# test_anta.net
KiCad netlist of a schematic drawn in Altium Designer
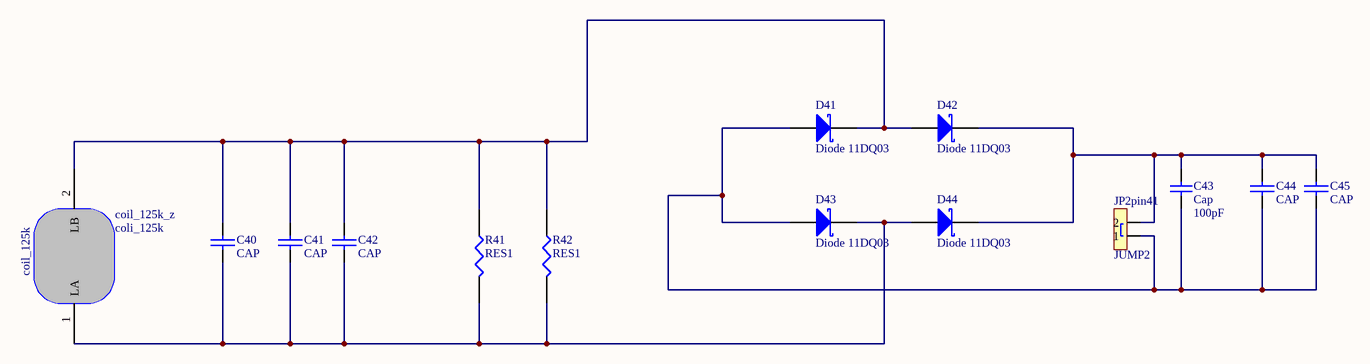
[diagram p0: test_anta.SchDoc]

(export (version "E")
  (design (tool "Eeschema 10.0.6"))
  (components
    (comp (ref "C40")
      (value "CAP")
      (footprint "C0805")
      (description "一般瓷片电容、直插选用RAD0.1，贴片选用0805")
      (libsource (lib "zqq_fmsh") (part "CAP"))
    )
    (comp (ref "C41")
      (value "CAP")
      (footprint "C0805")
      (description "一般瓷片电容、直插选用RAD0.1，贴片选用0805")
      (libsource (lib "zqq_fmsh") (part "CAP"))
    )
    (comp (ref "C42")
      (value "CAP")
      (footprint "RAD-0.3")
      (description "一般瓷片电容、直插选用RAD0.1，贴片选用0805")
      (libsource (lib "zqq_fmsh") (part "CAP"))
    )
    (comp (ref "C43")
      (value "Cap")
      (footprint "RAD-0.3")
      (description "Capacitor")
      (fields (field (name "ALTIUM_VALUE") "100pF") (field (name "PUBLISHER") "Altium Limited"))
      (libsource (lib "Miscellaneous Devices") (part "Cap"))
    )
    (comp (ref "C44")
      (value "CAP")
      (footprint "C0805")
      (description "一般瓷片电容、直插选用RAD0.1，贴片选用0805")
      (libsource (lib "zqq_fmsh") (part "CAP"))
    )
    (comp (ref "C45")
      (value "CAP")
      (footprint "C0805")
      (description "一般瓷片电容、直插选用RAD0.1，贴片选用0805")
      (libsource (lib "zqq_fmsh") (part "CAP"))
    )
    (comp (ref "coil_125k_z")
      (value "coli_125k")
      (footprint "coil_125k")
      (libsource (lib "pke") (part "coli_125k"))
    )
    (comp (ref "D41")
      (value "Diode 11DQ03")
      (footprint "DO-204AL")
      (description "Schottky Rectifier")
      (fields (field (name "PUBLISHER") "Altium Limited"))
      (libsource (lib "Miscellaneous Devices") (part "Diode 11DQ03"))
    )
    (comp (ref "D42")
      (value "Diode 11DQ03")
      (footprint "DO-204AL")
      (description "Schottky Rectifier")
      (fields (field (name "PUBLISHER") "Altium Limited"))
      (libsource (lib "Miscellaneous Devices") (part "Diode 11DQ03"))
    )
    (comp (ref "D43")
      (value "Diode 11DQ03")
      (footprint "DO-204AL")
      (description "Schottky Rectifier")
      (fields (field (name "PUBLISHER") "Altium Limited"))
      (libsource (lib "Miscellaneous Devices") (part "Diode 11DQ03"))
    )
    (comp (ref "D44")
      (value "Diode 11DQ03")
      (footprint "DO-204AL")
      (description "Schottky Rectifier")
      (fields (field (name "PUBLISHER") "Altium Limited"))
      (libsource (lib "Miscellaneous Devices") (part "Diode 11DQ03"))
    )
    (comp (ref "JP2pin41")
      (value "JUMP2")
      (footprint "HDR1X2")
      (description "单线跳线（短路）连接器，一般使用SIP2即可，当需要标示插件方向时可选SIP2-ST（间距2.54mm），当需要作短路线使用时可用SIP2-EASY-SHORT（间距2.54mm）")
      (libsource (lib "FM12XX Lib") (part "JUMP2"))
    )
    (comp (ref "R41")
      (value "RES1")
      (footprint "0805")
      (description "电阻，1/4w的金属膜直插可选AXIAL0.4封装（长度10mm），贴片可选0805封装，其他电阻可选AXIAL0.5～AXIAL1.0")
      (libsource (lib "FM12XX Lib") (part "RES1"))
    )
    (comp (ref "R42")
      (value "RES1")
      (footprint "0805")
      (description "电阻，1/4w的金属膜直插可选AXIAL0.4封装（长度10mm），贴片可选0805封装，其他电阻可选AXIAL0.5～AXIAL1.0")
      (libsource (lib "FM12XX Lib") (part "RES1"))
    )
  )
  (nets
    (net (code "1") (name "Net-(D41-A)") (class "Default")
      (node (ref "C43") (pin "1") (pinfunction "1_1") (pintype "passive"))
      (node (ref "C44") (pin "2") (pinfunction "2_2") (pintype "passive"))
      (node (ref "C45") (pin "2") (pinfunction "2_2") (pintype "passive"))
      (node (ref "D41") (pin "1") (pinfunction "A_1") (pintype "passive"))
      (node (ref "D43") (pin "1") (pinfunction "A_1") (pintype "passive"))
      (node (ref "JP2pin41") (pin "1") (pinfunction "1_1") (pintype "passive"))
    )
    (net (code "2") (name "Net-(D41-K)") (class "Default")
      (node (ref "C40") (pin "1") (pinfunction "1_1") (pintype "passive"))
      (node (ref "C41") (pin "1") (pinfunction "1_1") (pintype "passive"))
      (node (ref "C42") (pin "1") (pinfunction "1_1") (pintype "passive"))
      (node (ref "D41") (pin "2") (pinfunction "K_2") (pintype "passive"))
      (node (ref "D42") (pin "1") (pinfunction "A_1") (pintype "passive"))
      (node (ref "R41") (pin "1") (pinfunction "1_1") (pintype "passive"))
      (node (ref "R42") (pin "1") (pinfunction "1_1") (pintype "passive"))
      (node (ref "coil_125k_z") (pin "2") (pinfunction "LB_2") (pintype "passive"))
    )
    (net (code "3") (name "Net-(D42-K)") (class "Default")
      (node (ref "C43") (pin "2") (pinfunction "2_2") (pintype "passive"))
      (node (ref "C44") (pin "1") (pinfunction "1_1") (pintype "passive"))
      (node (ref "C45") (pin "1") (pinfunction "1_1") (pintype "passive"))
      (node (ref "D42") (pin "2") (pinfunction "K_2") (pintype "passive"))
      (node (ref "D44") (pin "2") (pinfunction "K_2") (pintype "passive"))
      (node (ref "JP2pin41") (pin "2") (pinfunction "2_2") (pintype "passive"))
    )
    (net (code "4") (name "Net-(D43-K)") (class "Default")
      (node (ref "C40") (pin "2") (pinfunction "2_2") (pintype "passive"))
      (node (ref "C41") (pin "2") (pinfunction "2_2") (pintype "passive"))
      (node (ref "C42") (pin "2") (pinfunction "2_2") (pintype "passive"))
      (node (ref "D43") (pin "2") (pinfunction "K_2") (pintype "passive"))
      (node (ref "D44") (pin "1") (pinfunction "A_1") (pintype "passive"))
      (node (ref "R41") (pin "2") (pinfunction "2_2") (pintype "passive"))
      (node (ref "R42") (pin "2") (pinfunction "2_2") (pintype "passive"))
      (node (ref "coil_125k_z") (pin "1") (pinfunction "LA_1") (pintype "passive"))
    )
  )
)
